# module_phase1.net
KiCad netlist of a schematic drawn in EAGLE
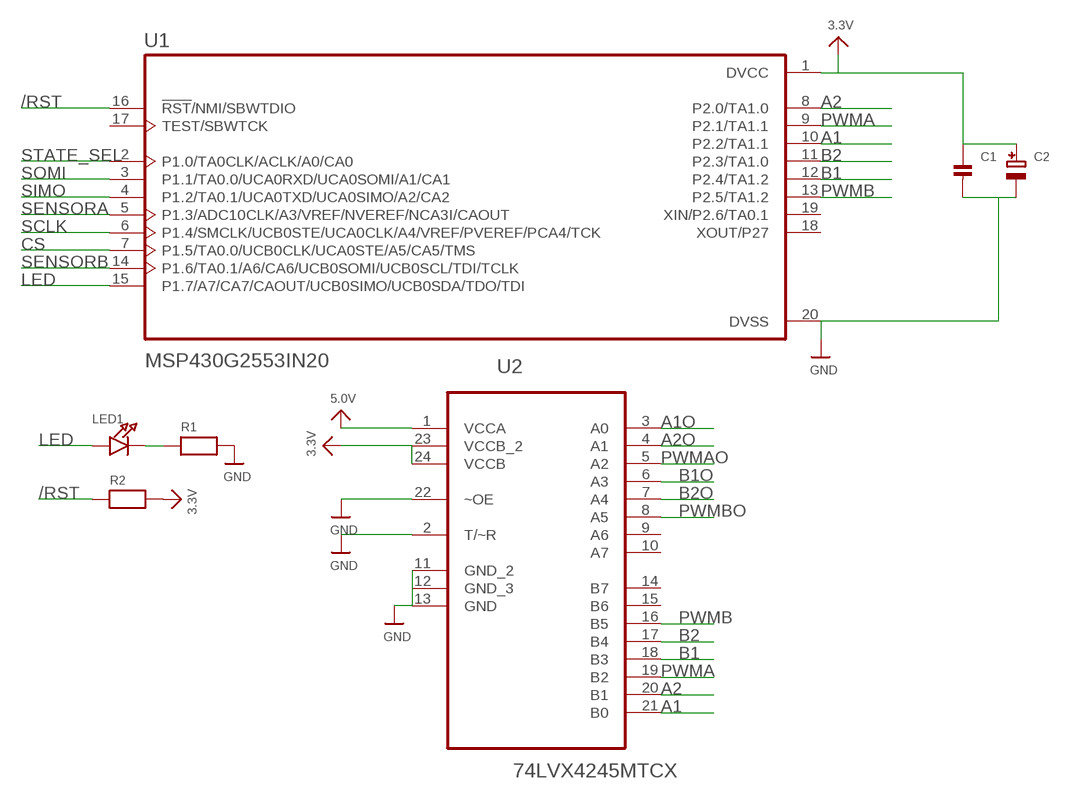
[diagram p0: schematic, sheet 1]

(export (version "E")
  (design (tool "Eeschema 10.0.6"))
  (components
    (comp (ref "C1")
      (value "CAP_CERAMIC0805")
      (footprint "eagle-import:0805")
      (libsource (lib "eagle-import") (part "CAP_CERAMIC0805"))
    )
    (comp (ref "C2")
      (value "CAP_ELECTROLYTICPANASONIC_C")
      (footprint "eagle-import:PANASONIC_C")
      (libsource (lib "eagle-import") (part "CAP_ELECTROLYTICPANASONIC_C"))
    )
    (comp (ref "LED1")
      (value "LED0805")
      (footprint "eagle-import:CHIPLED_0805")
      (libsource (lib "eagle-import") (part "LED0805"))
    )
    (comp (ref "R1")
      (value "RESISTOR0805")
      (footprint "eagle-import:0805")
      (libsource (lib "eagle-import") (part "RESISTOR0805"))
    )
    (comp (ref "R2")
      (value "RESISTOR0805")
      (footprint "eagle-import:0805")
      (libsource (lib "eagle-import") (part "RESISTOR0805"))
    )
    (comp (ref "U1")
      (value "MSP430G2553IN20")
      (footprint "eagle-import:DIP794W45P254L2692H508Q20")
      (fields (field (name "MF") "Texas Instruments"))
      (libsource (lib "eagle-import") (part "MSP430G2553IN20"))
    )
    (comp (ref "U2")
      (value "74LVX4245MTCX")
      (footprint "eagle-import:SOP65P640X90-24N")
      (fields (field (name "MF") "ON"))
      (libsource (lib "eagle-import") (part "74LVX4245MTCX"))
    )
  )
  (nets
    (net (code "1") (name "/A1") (class "Default")
      (node (ref "U1") (pin "10") (pinfunction "P2.2/TA1.1_10") (pintype "bidirectional"))
      (node (ref "U2") (pin "21") (pinfunction "B0_21") (pintype "output"))
    )
    (net (code "2") (name "/A1O") (class "Default")
      (node (ref "U2") (pin "3") (pinfunction "A0_3") (pintype "output"))
    )
    (net (code "3") (name "/A2") (class "Default")
      (node (ref "U1") (pin "8") (pinfunction "P2.0/TA1.0_8") (pintype "bidirectional"))
      (node (ref "U2") (pin "20") (pinfunction "B1_20") (pintype "output"))
    )
    (net (code "4") (name "/A2O") (class "Default")
      (node (ref "U2") (pin "4") (pinfunction "A1_4") (pintype "output"))
    )
    (net (code "5") (name "/B1") (class "Default")
      (node (ref "U1") (pin "12") (pinfunction "P2.4/TA1.2_12") (pintype "bidirectional"))
      (node (ref "U2") (pin "18") (pinfunction "B3_18") (pintype "output"))
    )
    (net (code "6") (name "/B1O") (class "Default")
      (node (ref "U2") (pin "6") (pinfunction "A3_6") (pintype "output"))
    )
    (net (code "7") (name "/B2") (class "Default")
      (node (ref "U1") (pin "11") (pinfunction "P2.3/TA1.0_11") (pintype "bidirectional"))
      (node (ref "U2") (pin "17") (pinfunction "B4_17") (pintype "output"))
    )
    (net (code "8") (name "/B2O") (class "Default")
      (node (ref "U2") (pin "7") (pinfunction "A4_7") (pintype "output"))
    )
    (net (code "9") (name "/CS") (class "Default")
      (node (ref "U1") (pin "7") (pinfunction "P1.5/TA0.0/UCB0CLK/UCA0STE/A5/CA5/TMS_7") (pintype "bidirectional"))
    )
    (net (code "10") (name "/LED") (class "Default")
      (node (ref "LED1") (pin "A") (pinfunction "A_A") (pintype "passive"))
      (node (ref "U1") (pin "15") (pinfunction "P1.7/A7/CA7/CAOUT/UCB0SIMO/UCB0SDA/TDO/TDI_15") (pintype "bidirectional"))
    )
    (net (code "11") (name "/PWMA") (class "Default")
      (node (ref "U1") (pin "9") (pinfunction "P2.1/TA1.1_9") (pintype "bidirectional"))
      (node (ref "U2") (pin "19") (pinfunction "B2_19") (pintype "output"))
    )
    (net (code "12") (name "/PWMAO") (class "Default")
      (node (ref "U2") (pin "5") (pinfunction "A2_5") (pintype "output"))
    )
    (net (code "13") (name "/PWMB") (class "Default")
      (node (ref "U1") (pin "13") (pinfunction "P2.5/TA1.2_13") (pintype "bidirectional"))
      (node (ref "U2") (pin "16") (pinfunction "B5_16") (pintype "output"))
    )
    (net (code "14") (name "/PWMBO") (class "Default")
      (node (ref "U2") (pin "8") (pinfunction "A5_8") (pintype "output"))
    )
    (net (code "15") (name "/SCLK") (class "Default")
      (node (ref "U1") (pin "6") (pinfunction "P1.4/SMCLK/UCB0STE/UCA0CLK/A4/VREF/PVEREF/PCA4/TCK_6") (pintype "bidirectional"))
    )
    (net (code "16") (name "/SENSORA") (class "Default")
      (node (ref "U1") (pin "5") (pinfunction "P1.3/ADC10CLK/A3/VREF/NVEREF/NCA3I/CAOUT_5") (pintype "bidirectional"))
    )
    (net (code "17") (name "/SENSORB") (class "Default")
      (node (ref "U1") (pin "14") (pinfunction "P1.6/TA0.1/A6/CA6/UCB0SOMI/UCB0SCL/TDI/TCLK_14") (pintype "bidirectional"))
    )
    (net (code "18") (name "/SIMO") (class "Default")
      (node (ref "U1") (pin "4") (pinfunction "P1.2/TA0.1/UCA0TXD/UCA0SIMO/A2/CA2_4") (pintype "bidirectional"))
    )
    (net (code "19") (name "/SOMI") (class "Default")
      (node (ref "U1") (pin "3") (pinfunction "P1.1/TA0.0/UCA0RXD/UCA0SOMI/A1/CA1_3") (pintype "bidirectional"))
    )
    (net (code "20") (name "/STATE_SEL") (class "Default")
      (node (ref "U1") (pin "2") (pinfunction "P1.0/TA0CLK/ACLK/A0/CA0_2") (pintype "bidirectional"))
    )
    (net (code "21") (name "/{slash}RST") (class "Default")
      (node (ref "R2") (pin "1") (pinfunction "1_1") (pintype "passive"))
      (node (ref "U1") (pin "16") (pinfunction "~{RST}/NMI/SBWTDIO_16") (pintype "input"))
    )
    (net (code "22") (name "3.3V") (class "Default")
      (node (ref "C1") (pin "1") (pinfunction "P$1_1") (pintype "passive"))
      (node (ref "C2") (pin "+") (pinfunction "+_+") (pintype "passive"))
      (node (ref "R2") (pin "2") (pinfunction "2_2") (pintype "passive"))
      (node (ref "U1") (pin "1") (pinfunction "DVCC_1") (pintype "power_in"))
      (node (ref "U2") (pin "23") (pinfunction "VCCB_2_23") (pintype "power_in"))
      (node (ref "U2") (pin "24") (pinfunction "VCCB_24") (pintype "power_in"))
    )
    (net (code "23") (name "5.0V") (class "Default")
      (node (ref "U2") (pin "1") (pinfunction "VCCA_1") (pintype "power_in"))
    )
    (net (code "24") (name "GND") (class "Default")
      (node (ref "C1") (pin "2") (pinfunction "P$2_2") (pintype "passive"))
      (node (ref "C2") (pin "-") (pinfunction "-_-") (pintype "passive"))
      (node (ref "R1") (pin "2") (pinfunction "2_2") (pintype "passive"))
      (node (ref "U1") (pin "20") (pinfunction "DVSS_20") (pintype "power_in"))
      (node (ref "U2") (pin "11") (pinfunction "GND_2_11") (pintype "passive"))
      (node (ref "U2") (pin "12") (pinfunction "GND_3_12") (pintype "passive"))
      (node (ref "U2") (pin "13") (pinfunction "GND_13") (pintype "passive"))
      (node (ref "U2") (pin "2") (pinfunction "T/~{R}_2") (pintype "input"))
      (node (ref "U2") (pin "22") (pinfunction "~{OE}_22") (pintype "input"))
    )
    (net (code "25") (name "Net-(LED1-PadC)") (class "Default")
      (node (ref "LED1") (pin "C") (pinfunction "C_C") (pintype "passive"))
      (node (ref "R1") (pin "1") (pinfunction "1_1") (pintype "passive"))
    )
    (net (code "26") (name "unconnected-(U1-TEST{slash}SBWTCK-Pad17)") (class "Default")
      (node (ref "U1") (pin "17") (pinfunction "TEST/SBWTCK_17") (pintype "input"))
    )
    (net (code "27") (name "unconnected-(U1-XIN{slash}P2.6{slash}TA0.1-Pad19)") (class "Default")
      (node (ref "U1") (pin "19") (pinfunction "XIN/P2.6/TA0.1_19") (pintype "bidirectional"))
    )
    (net (code "28") (name "unconnected-(U1-XOUT{slash}P27-Pad18)") (class "Default")
      (node (ref "U1") (pin "18") (pinfunction "XOUT/P27_18") (pintype "bidirectional"))
    )
    (net (code "29") (name "unconnected-(U2-A6-Pad9)") (class "Default")
      (node (ref "U2") (pin "9") (pinfunction "A6_9") (pintype "output"))
    )
    (net (code "30") (name "unconnected-(U2-A7-Pad10)") (class "Default")
      (node (ref "U2") (pin "10") (pinfunction "A7_10") (pintype "output"))
    )
    (net (code "31") (name "unconnected-(U2-B6-Pad15)") (class "Default")
      (node (ref "U2") (pin "15") (pinfunction "B6_15") (pintype "output"))
    )
    (net (code "32") (name "unconnected-(U2-B7-Pad14)") (class "Default")
      (node (ref "U2") (pin "14") (pinfunction "B7_14") (pintype "output"))
    )
  )
)
